# radiata_v1.net
KiCad netlist of a schematic drawn in EAGLE
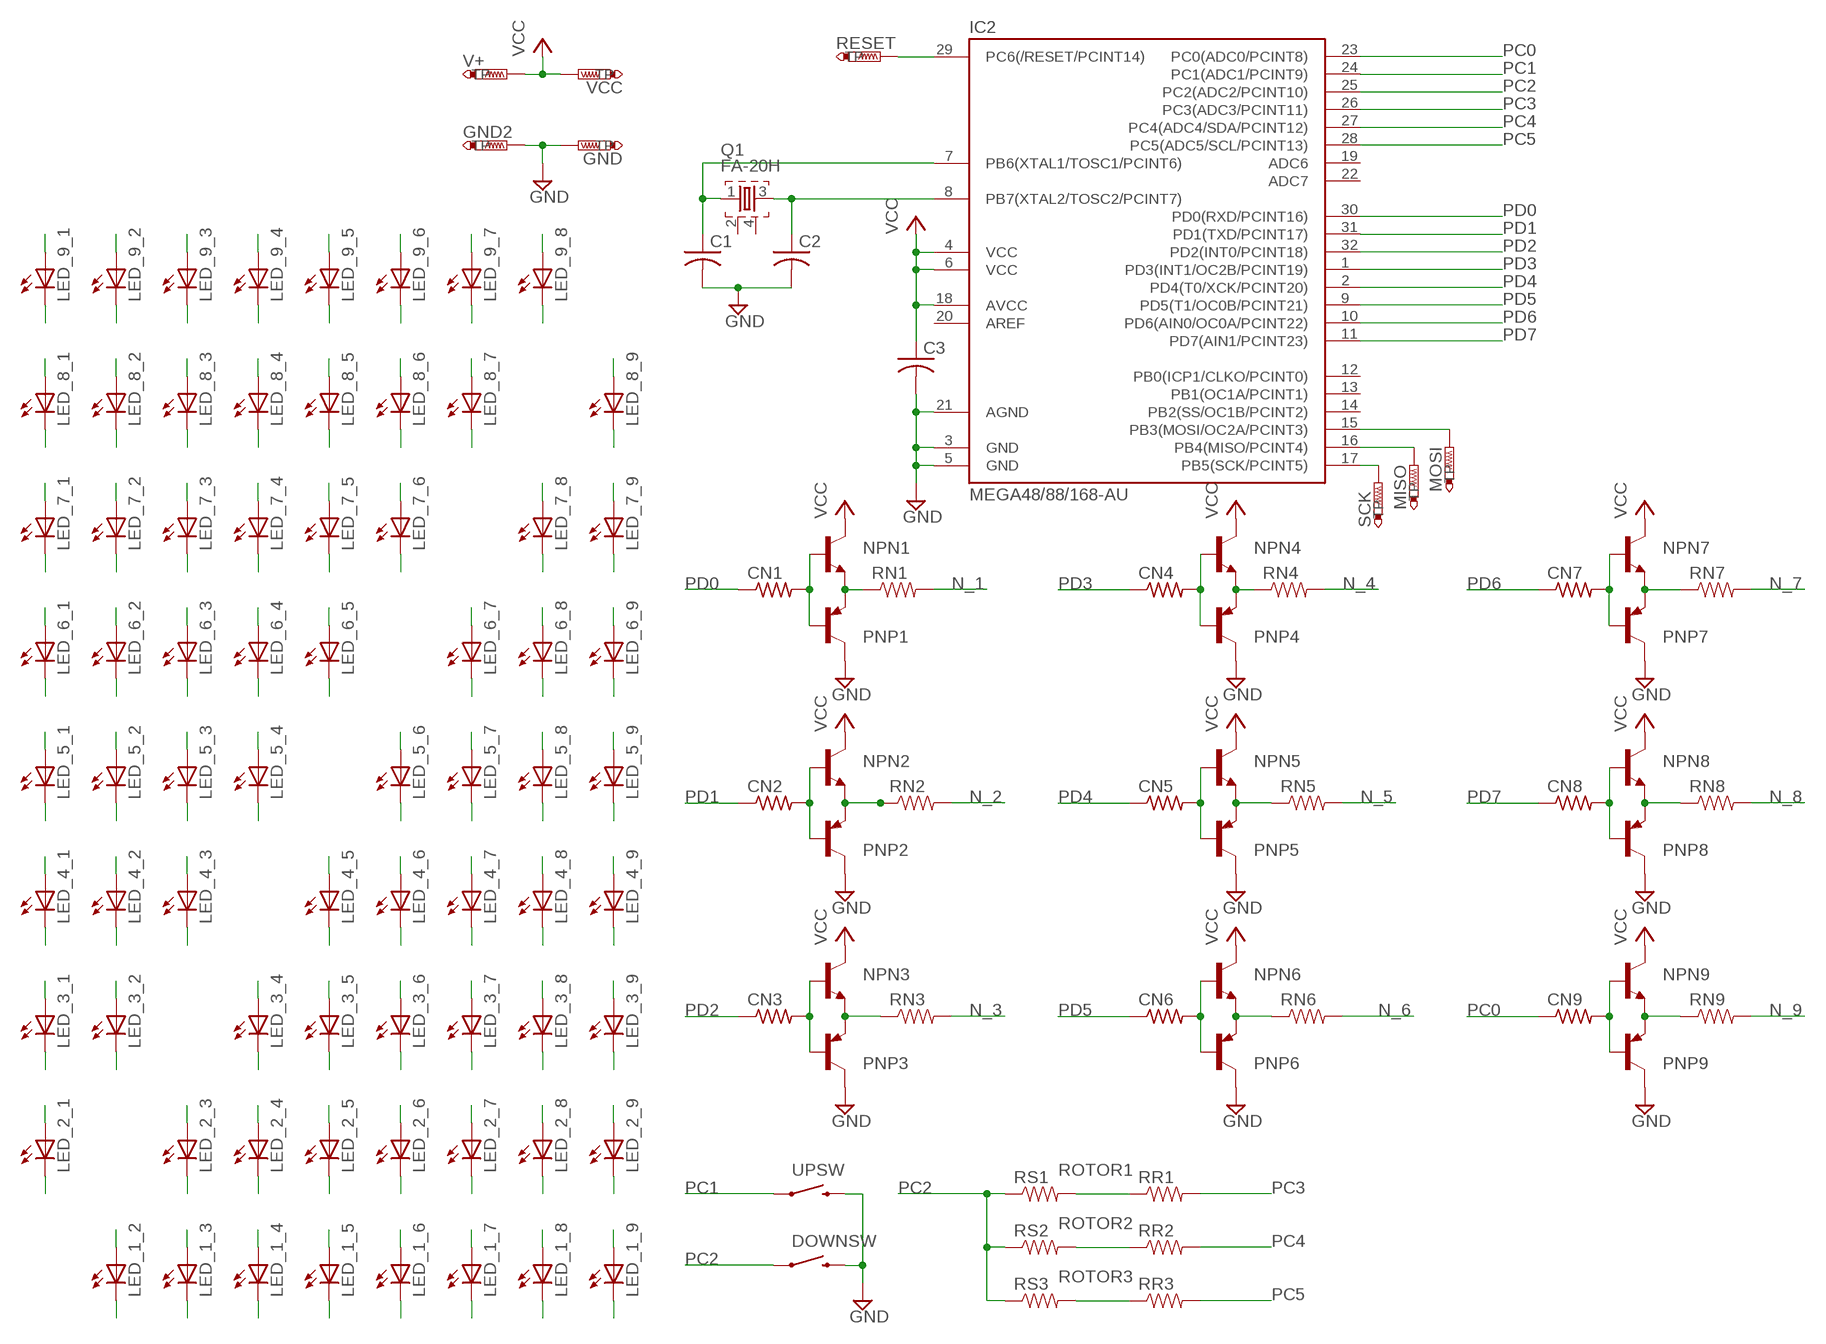
[diagram p0: schematic, sheet 1]

(export (version "E")
  (design (tool "Eeschema 10.0.6"))
  (components
    (comp (ref "C1")
      (value "C-USC0603")
      (footprint "eagle-import:C0603")
      (libsource (lib "eagle-import") (part "C-USC0603"))
    )
    (comp (ref "C2")
      (value "C-USC0603")
      (footprint "eagle-import:C0603")
      (libsource (lib "eagle-import") (part "C-USC0603"))
    )
    (comp (ref "C3")
      (value "C-USC0603")
      (footprint "eagle-import:C0603")
      (libsource (lib "eagle-import") (part "C-USC0603"))
    )
    (comp (ref "CN1")
      (value "R-US_M0805")
      (footprint "eagle-import:M0805")
      (libsource (lib "eagle-import") (part "R-US_M0805"))
    )
    (comp (ref "CN2")
      (value "R-US_M0805")
      (footprint "eagle-import:M0805")
      (libsource (lib "eagle-import") (part "R-US_M0805"))
    )
    (comp (ref "CN3")
      (value "R-US_M0805")
      (footprint "eagle-import:M0805")
      (libsource (lib "eagle-import") (part "R-US_M0805"))
    )
    (comp (ref "CN4")
      (value "R-US_M0805")
      (footprint "eagle-import:M0805")
      (libsource (lib "eagle-import") (part "R-US_M0805"))
    )
    (comp (ref "CN5")
      (value "R-US_M0805")
      (footprint "eagle-import:M0805")
      (libsource (lib "eagle-import") (part "R-US_M0805"))
    )
    (comp (ref "CN6")
      (value "R-US_M0805")
      (footprint "eagle-import:M0805")
      (libsource (lib "eagle-import") (part "R-US_M0805"))
    )
    (comp (ref "CN7")
      (value "R-US_M0805")
      (footprint "eagle-import:M0805")
      (libsource (lib "eagle-import") (part "R-US_M0805"))
    )
    (comp (ref "CN8")
      (value "R-US_M0805")
      (footprint "eagle-import:M0805")
      (libsource (lib "eagle-import") (part "R-US_M0805"))
    )
    (comp (ref "CN9")
      (value "R-US_M0805")
      (footprint "eagle-import:M0805")
      (libsource (lib "eagle-import") (part "R-US_M0805"))
    )
    (comp (ref "DOWNSW")
      (value "SWITCH-MOMENTARY-2")
      (footprint "eagle-import:TACTILE_SWITCH_TALL")
      (libsource (lib "eagle-import") (part "SWITCH-MOMENTARY-2"))
    )
    (comp (ref "GND")
      (value "PTR1TP19R")
      (footprint "eagle-import:TP19R")
      (libsource (lib "eagle-import") (part "PTR1TP19R"))
    )
    (comp (ref "GND2")
      (value "PTR1TP20SQ")
      (footprint "eagle-import:TP20SQ")
      (libsource (lib "eagle-import") (part "PTR1TP20SQ"))
    )
    (comp (ref "IC2")
      (value "MEGA48/88/168-AU")
      (footprint "eagle-import:TQFP32-08")
      (libsource (lib "eagle-import") (part "MEGA48/88/168-AU"))
    )
    (comp (ref "LED_1_2")
      (value "LEDCHIPLED_1206")
      (footprint "eagle-import:CHIPLED_1206")
      (libsource (lib "eagle-import") (part "LEDCHIPLED_1206"))
    )
    (comp (ref "LED_1_3")
      (value "LEDCHIPLED_1206")
      (footprint "eagle-import:CHIPLED_1206")
      (libsource (lib "eagle-import") (part "LEDCHIPLED_1206"))
    )
    (comp (ref "LED_1_4")
      (value "LEDCHIPLED_1206")
      (footprint "eagle-import:CHIPLED_1206")
      (libsource (lib "eagle-import") (part "LEDCHIPLED_1206"))
    )
    (comp (ref "LED_1_5")
      (value "LEDCHIPLED_1206")
      (footprint "eagle-import:CHIPLED_1206")
      (libsource (lib "eagle-import") (part "LEDCHIPLED_1206"))
    )
    (comp (ref "LED_1_6")
      (value "LEDCHIPLED_1206")
      (footprint "eagle-import:CHIPLED_1206")
      (libsource (lib "eagle-import") (part "LEDCHIPLED_1206"))
    )
    (comp (ref "LED_1_7")
      (value "LEDCHIPLED_1206")
      (footprint "eagle-import:CHIPLED_1206")
      (libsource (lib "eagle-import") (part "LEDCHIPLED_1206"))
    )
    (comp (ref "LED_1_8")
      (value "LEDCHIPLED_1206")
      (footprint "eagle-import:CHIPLED_1206")
      (libsource (lib "eagle-import") (part "LEDCHIPLED_1206"))
    )
    (comp (ref "LED_1_9")
      (value "LEDCHIPLED_1206")
      (footprint "eagle-import:CHIPLED_1206")
      (libsource (lib "eagle-import") (part "LEDCHIPLED_1206"))
    )
    (comp (ref "LED_2_1")
      (value "LEDCHIPLED_1206")
      (footprint "eagle-import:CHIPLED_1206")
      (libsource (lib "eagle-import") (part "LEDCHIPLED_1206"))
    )
    (comp (ref "LED_2_3")
      (value "LEDCHIPLED_1206")
      (footprint "eagle-import:CHIPLED_1206")
      (libsource (lib "eagle-import") (part "LEDCHIPLED_1206"))
    )
    (comp (ref "LED_2_4")
      (value "LEDCHIPLED_1206")
      (footprint "eagle-import:CHIPLED_1206")
      (libsource (lib "eagle-import") (part "LEDCHIPLED_1206"))
    )
    (comp (ref "LED_2_5")
      (value "LEDCHIPLED_1206")
      (footprint "eagle-import:CHIPLED_1206")
      (libsource (lib "eagle-import") (part "LEDCHIPLED_1206"))
    )
    (comp (ref "LED_2_6")
      (value "LEDCHIPLED_1206")
      (footprint "eagle-import:CHIPLED_1206")
      (libsource (lib "eagle-import") (part "LEDCHIPLED_1206"))
    )
    (comp (ref "LED_2_7")
      (value "LEDCHIPLED_1206")
      (footprint "eagle-import:CHIPLED_1206")
      (libsource (lib "eagle-import") (part "LEDCHIPLED_1206"))
    )
    (comp (ref "LED_2_8")
      (value "LEDCHIPLED_1206")
      (footprint "eagle-import:CHIPLED_1206")
      (libsource (lib "eagle-import") (part "LEDCHIPLED_1206"))
    )
    (comp (ref "LED_2_9")
      (value "LEDCHIPLED_1206")
      (footprint "eagle-import:CHIPLED_1206")
      (libsource (lib "eagle-import") (part "LEDCHIPLED_1206"))
    )
    (comp (ref "LED_3_1")
      (value "LEDCHIPLED_1206")
      (footprint "eagle-import:CHIPLED_1206")
      (libsource (lib "eagle-import") (part "LEDCHIPLED_1206"))
    )
    (comp (ref "LED_3_2")
      (value "LEDCHIPLED_1206")
      (footprint "eagle-import:CHIPLED_1206")
      (libsource (lib "eagle-import") (part "LEDCHIPLED_1206"))
    )
    (comp (ref "LED_3_4")
      (value "LEDCHIPLED_1206")
      (footprint "eagle-import:CHIPLED_1206")
      (libsource (lib "eagle-import") (part "LEDCHIPLED_1206"))
    )
    (comp (ref "LED_3_5")
      (value "LEDCHIPLED_1206")
      (footprint "eagle-import:CHIPLED_1206")
      (libsource (lib "eagle-import") (part "LEDCHIPLED_1206"))
    )
    (comp (ref "LED_3_6")
      (value "LEDCHIPLED_1206")
      (footprint "eagle-import:CHIPLED_1206")
      (libsource (lib "eagle-import") (part "LEDCHIPLED_1206"))
    )
    (comp (ref "LED_3_7")
      (value "LEDCHIPLED_1206")
      (footprint "eagle-import:CHIPLED_1206")
      (libsource (lib "eagle-import") (part "LEDCHIPLED_1206"))
    )
    (comp (ref "LED_3_8")
      (value "LEDCHIPLED_1206")
      (footprint "eagle-import:CHIPLED_1206")
      (libsource (lib "eagle-import") (part "LEDCHIPLED_1206"))
    )
    (comp (ref "LED_3_9")
      (value "LEDCHIPLED_1206")
      (footprint "eagle-import:CHIPLED_1206")
      (libsource (lib "eagle-import") (part "LEDCHIPLED_1206"))
    )
    (comp (ref "LED_4_1")
      (value "LEDCHIPLED_1206")
      (footprint "eagle-import:CHIPLED_1206")
      (libsource (lib "eagle-import") (part "LEDCHIPLED_1206"))
    )
    (comp (ref "LED_4_2")
      (value "LEDCHIPLED_1206")
      (footprint "eagle-import:CHIPLED_1206")
      (libsource (lib "eagle-import") (part "LEDCHIPLED_1206"))
    )
    (comp (ref "LED_4_3")
      (value "LEDCHIPLED_1206")
      (footprint "eagle-import:CHIPLED_1206")
      (libsource (lib "eagle-import") (part "LEDCHIPLED_1206"))
    )
    (comp (ref "LED_4_5")
      (value "LEDCHIPLED_1206")
      (footprint "eagle-import:CHIPLED_1206")
      (libsource (lib "eagle-import") (part "LEDCHIPLED_1206"))
    )
    (comp (ref "LED_4_6")
      (value "LEDCHIPLED_1206")
      (footprint "eagle-import:CHIPLED_1206")
      (libsource (lib "eagle-import") (part "LEDCHIPLED_1206"))
    )
    (comp (ref "LED_4_7")
      (value "LEDCHIPLED_1206")
      (footprint "eagle-import:CHIPLED_1206")
      (libsource (lib "eagle-import") (part "LEDCHIPLED_1206"))
    )
    (comp (ref "LED_4_8")
      (value "LEDCHIPLED_1206")
      (footprint "eagle-import:CHIPLED_1206")
      (libsource (lib "eagle-import") (part "LEDCHIPLED_1206"))
    )
    (comp (ref "LED_4_9")
      (value "LEDCHIPLED_1206")
      (footprint "eagle-import:CHIPLED_1206")
      (libsource (lib "eagle-import") (part "LEDCHIPLED_1206"))
    )
    (comp (ref "LED_5_1")
      (value "LEDCHIPLED_1206")
      (footprint "eagle-import:CHIPLED_1206")
      (libsource (lib "eagle-import") (part "LEDCHIPLED_1206"))
    )
    (comp (ref "LED_5_2")
      (value "LEDCHIPLED_1206")
      (footprint "eagle-import:CHIPLED_1206")
      (libsource (lib "eagle-import") (part "LEDCHIPLED_1206"))
    )
    (comp (ref "LED_5_3")
      (value "LEDCHIPLED_1206")
      (footprint "eagle-import:CHIPLED_1206")
      (libsource (lib "eagle-import") (part "LEDCHIPLED_1206"))
    )
    (comp (ref "LED_5_4")
      (value "LEDCHIPLED_1206")
      (footprint "eagle-import:CHIPLED_1206")
      (libsource (lib "eagle-import") (part "LEDCHIPLED_1206"))
    )
    (comp (ref "LED_5_6")
      (value "LEDCHIPLED_1206")
      (footprint "eagle-import:CHIPLED_1206")
      (libsource (lib "eagle-import") (part "LEDCHIPLED_1206"))
    )
    (comp (ref "LED_5_7")
      (value "LEDCHIPLED_1206")
      (footprint "eagle-import:CHIPLED_1206")
      (libsource (lib "eagle-import") (part "LEDCHIPLED_1206"))
    )
    (comp (ref "LED_5_8")
      (value "LEDCHIPLED_1206")
      (footprint "eagle-import:CHIPLED_1206")
      (libsource (lib "eagle-import") (part "LEDCHIPLED_1206"))
    )
    (comp (ref "LED_5_9")
      (value "LEDCHIPLED_1206")
      (footprint "eagle-import:CHIPLED_1206")
      (libsource (lib "eagle-import") (part "LEDCHIPLED_1206"))
    )
    (comp (ref "LED_6_1")
      (value "LEDCHIPLED_1206")
      (footprint "eagle-import:CHIPLED_1206")
      (libsource (lib "eagle-import") (part "LEDCHIPLED_1206"))
    )
    (comp (ref "LED_6_2")
      (value "LEDCHIPLED_1206")
      (footprint "eagle-import:CHIPLED_1206")
      (libsource (lib "eagle-import") (part "LEDCHIPLED_1206"))
    )
    (comp (ref "LED_6_3")
      (value "LEDCHIPLED_1206")
      (footprint "eagle-import:CHIPLED_1206")
      (libsource (lib "eagle-import") (part "LEDCHIPLED_1206"))
    )
    (comp (ref "LED_6_4")
      (value "LEDCHIPLED_1206")
      (footprint "eagle-import:CHIPLED_1206")
      (libsource (lib "eagle-import") (part "LEDCHIPLED_1206"))
    )
    (comp (ref "LED_6_5")
      (value "LEDCHIPLED_1206")
      (footprint "eagle-import:CHIPLED_1206")
      (libsource (lib "eagle-import") (part "LEDCHIPLED_1206"))
    )
    (comp (ref "LED_6_7")
      (value "LEDCHIPLED_1206")
      (footprint "eagle-import:CHIPLED_1206")
      (libsource (lib "eagle-import") (part "LEDCHIPLED_1206"))
    )
    (comp (ref "LED_6_8")
      (value "LEDCHIPLED_1206")
      (footprint "eagle-import:CHIPLED_1206")
      (libsource (lib "eagle-import") (part "LEDCHIPLED_1206"))
    )
    (comp (ref "LED_6_9")
      (value "LEDCHIPLED_1206")
      (footprint "eagle-import:CHIPLED_1206")
      (libsource (lib "eagle-import") (part "LEDCHIPLED_1206"))
    )
    (comp (ref "LED_7_1")
      (value "LEDCHIPLED_1206")
      (footprint "eagle-import:CHIPLED_1206")
      (libsource (lib "eagle-import") (part "LEDCHIPLED_1206"))
    )
    (comp (ref "LED_7_2")
      (value "LEDCHIPLED_1206")
      (footprint "eagle-import:CHIPLED_1206")
      (libsource (lib "eagle-import") (part "LEDCHIPLED_1206"))
    )
    (comp (ref "LED_7_3")
      (value "LEDCHIPLED_1206")
      (footprint "eagle-import:CHIPLED_1206")
      (libsource (lib "eagle-import") (part "LEDCHIPLED_1206"))
    )
    (comp (ref "LED_7_4")
      (value "LEDCHIPLED_1206")
      (footprint "eagle-import:CHIPLED_1206")
      (libsource (lib "eagle-import") (part "LEDCHIPLED_1206"))
    )
    (comp (ref "LED_7_5")
      (value "LEDCHIPLED_1206")
      (footprint "eagle-import:CHIPLED_1206")
      (libsource (lib "eagle-import") (part "LEDCHIPLED_1206"))
    )
    (comp (ref "LED_7_6")
      (value "LEDCHIPLED_1206")
      (footprint "eagle-import:CHIPLED_1206")
      (libsource (lib "eagle-import") (part "LEDCHIPLED_1206"))
    )
    (comp (ref "LED_7_8")
      (value "LEDCHIPLED_1206")
      (footprint "eagle-import:CHIPLED_1206")
      (libsource (lib "eagle-import") (part "LEDCHIPLED_1206"))
    )
    (comp (ref "LED_7_9")
      (value "LEDCHIPLED_1206")
      (footprint "eagle-import:CHIPLED_1206")
      (libsource (lib "eagle-import") (part "LEDCHIPLED_1206"))
    )
    (comp (ref "LED_8_1")
      (value "LEDCHIPLED_1206")
      (footprint "eagle-import:CHIPLED_1206")
      (libsource (lib "eagle-import") (part "LEDCHIPLED_1206"))
    )
    (comp (ref "LED_8_2")
      (value "LEDCHIPLED_1206")
      (footprint "eagle-import:CHIPLED_1206")
      (libsource (lib "eagle-import") (part "LEDCHIPLED_1206"))
    )
    (comp (ref "LED_8_3")
      (value "LEDCHIPLED_1206")
      (footprint "eagle-import:CHIPLED_1206")
      (libsource (lib "eagle-import") (part "LEDCHIPLED_1206"))
    )
    (comp (ref "LED_8_4")
      (value "LEDCHIPLED_1206")
      (footprint "eagle-import:CHIPLED_1206")
      (libsource (lib "eagle-import") (part "LEDCHIPLED_1206"))
    )
    (comp (ref "LED_8_5")
      (value "LEDCHIPLED_1206")
      (footprint "eagle-import:CHIPLED_1206")
      (libsource (lib "eagle-import") (part "LEDCHIPLED_1206"))
    )
    (comp (ref "LED_8_6")
      (value "LEDCHIPLED_1206")
      (footprint "eagle-import:CHIPLED_1206")
      (libsource (lib "eagle-import") (part "LEDCHIPLED_1206"))
    )
    (comp (ref "LED_8_7")
      (value "LEDCHIPLED_1206")
      (footprint "eagle-import:CHIPLED_1206")
      (libsource (lib "eagle-import") (part "LEDCHIPLED_1206"))
    )
    (comp (ref "LED_8_9")
      (value "LEDCHIPLED_1206")
      (footprint "eagle-import:CHIPLED_1206")
      (libsource (lib "eagle-import") (part "LEDCHIPLED_1206"))
    )
    (comp (ref "LED_9_1")
      (value "LEDCHIPLED_1206")
      (footprint "eagle-import:CHIPLED_1206")
      (libsource (lib "eagle-import") (part "LEDCHIPLED_1206"))
    )
    (comp (ref "LED_9_2")
      (value "LEDCHIPLED_1206")
      (footprint "eagle-import:CHIPLED_1206")
      (libsource (lib "eagle-import") (part "LEDCHIPLED_1206"))
    )
    (comp (ref "LED_9_3")
      (value "LEDCHIPLED_1206")
      (footprint "eagle-import:CHIPLED_1206")
      (libsource (lib "eagle-import") (part "LEDCHIPLED_1206"))
    )
    (comp (ref "LED_9_4")
      (value "LEDCHIPLED_1206")
      (footprint "eagle-import:CHIPLED_1206")
      (libsource (lib "eagle-import") (part "LEDCHIPLED_1206"))
    )
    (comp (ref "LED_9_5")
      (value "LEDCHIPLED_1206")
      (footprint "eagle-import:CHIPLED_1206")
      (libsource (lib "eagle-import") (part "LEDCHIPLED_1206"))
    )
    (comp (ref "LED_9_6")
      (value "LEDCHIPLED_1206")
      (footprint "eagle-import:CHIPLED_1206")
      (libsource (lib "eagle-import") (part "LEDCHIPLED_1206"))
    )
    (comp (ref "LED_9_7")
      (value "LEDCHIPLED_1206")
      (footprint "eagle-import:CHIPLED_1206")
      (libsource (lib "eagle-import") (part "LEDCHIPLED_1206"))
    )
    (comp (ref "LED_9_8")
      (value "LEDCHIPLED_1206")
      (footprint "eagle-import:CHIPLED_1206")
      (libsource (lib "eagle-import") (part "LEDCHIPLED_1206"))
    )
    (comp (ref "MISO")
      (value "PTR1TP19R")
      (footprint "eagle-import:TP19R")
      (libsource (lib "eagle-import") (part "PTR1TP19R"))
    )
    (comp (ref "MOSI")
      (value "PTR1TP19R")
      (footprint "eagle-import:TP19R")
      (libsource (lib "eagle-import") (part "PTR1TP19R"))
    )
    (comp (ref "NPN1")
      (value "MMBT2222ALT1-NPN-SOT23-BEC")
      (footprint "eagle-import:SOT23-BEC")
      (libsource (lib "eagle-import") (part "-NPN-SOT23-BECMMBT2222ALT1"))
    )
    (comp (ref "NPN2")
      (value "MMBT2222ALT1-NPN-SOT23-BEC")
      (footprint "eagle-import:SOT23-BEC")
      (libsource (lib "eagle-import") (part "-NPN-SOT23-BECMMBT2222ALT1"))
    )
    (comp (ref "NPN3")
      (value "MMBT2222ALT1-NPN-SOT23-BEC")
      (footprint "eagle-import:SOT23-BEC")
      (libsource (lib "eagle-import") (part "-NPN-SOT23-BECMMBT2222ALT1"))
    )
    (comp (ref "NPN4")
      (value "MMBT2222ALT1-NPN-SOT23-BEC")
      (footprint "eagle-import:SOT23-BEC")
      (libsource (lib "eagle-import") (part "-NPN-SOT23-BECMMBT2222ALT1"))
    )
    (comp (ref "NPN5")
      (value "MMBT2222ALT1-NPN-SOT23-BEC")
      (footprint "eagle-import:SOT23-BEC")
      (libsource (lib "eagle-import") (part "-NPN-SOT23-BECMMBT2222ALT1"))
    )
    (comp (ref "NPN6")
      (value "MMBT2222ALT1-NPN-SOT23-BEC")
      (footprint "eagle-import:SOT23-BEC")
      (libsource (lib "eagle-import") (part "-NPN-SOT23-BECMMBT2222ALT1"))
    )
    (comp (ref "NPN7")
      (value "MMBT2222ALT1-NPN-SOT23-BEC")
      (footprint "eagle-import:SOT23-BEC")
      (libsource (lib "eagle-import") (part "-NPN-SOT23-BECMMBT2222ALT1"))
    )
    (comp (ref "NPN8")
      (value "MMBT2222ALT1-NPN-SOT23-BEC")
      (footprint "eagle-import:SOT23-BEC")
      (libsource (lib "eagle-import") (part "-NPN-SOT23-BECMMBT2222ALT1"))
    )
    (comp (ref "NPN9")
      (value "MMBT2222ALT1-NPN-SOT23-BEC")
      (footprint "eagle-import:SOT23-BEC")
      (libsource (lib "eagle-import") (part "-NPN-SOT23-BECMMBT2222ALT1"))
    )
    (comp (ref "PNP1")
      (value "MMBT2907ALT1-PNP-SOT23-BEC")
      (footprint "eagle-import:SOT23-BEC")
      (libsource (lib "eagle-import") (part "-PNP-SOT23-BECMMBT2907ALT1"))
    )
    (comp (ref "PNP2")
      (value "MMBT2907ALT1-PNP-SOT23-BEC")
      (footprint "eagle-import:SOT23-BEC")
      (libsource (lib "eagle-import") (part "-PNP-SOT23-BECMMBT2907ALT1"))
    )
    (comp (ref "PNP3")
      (value "MMBT2907ALT1-PNP-SOT23-BEC")
      (footprint "eagle-import:SOT23-BEC")
      (libsource (lib "eagle-import") (part "-PNP-SOT23-BECMMBT2907ALT1"))
    )
    (comp (ref "PNP4")
      (value "MMBT2907ALT1-PNP-SOT23-BEC")
      (footprint "eagle-import:SOT23-BEC")
      (libsource (lib "eagle-import") (part "-PNP-SOT23-BECMMBT2907ALT1"))
    )
    (comp (ref "PNP5")
      (value "MMBT2907ALT1-PNP-SOT23-BEC")
      (footprint "eagle-import:SOT23-BEC")
      (libsource (lib "eagle-import") (part "-PNP-SOT23-BECMMBT2907ALT1"))
    )
    (comp (ref "PNP6")
      (value "MMBT2907ALT1-PNP-SOT23-BEC")
      (footprint "eagle-import:SOT23-BEC")
      (libsource (lib "eagle-import") (part "-PNP-SOT23-BECMMBT2907ALT1"))
    )
    (comp (ref "PNP7")
      (value "MMBT2907ALT1-PNP-SOT23-BEC")
      (footprint "eagle-import:SOT23-BEC")
      (libsource (lib "eagle-import") (part "-PNP-SOT23-BECMMBT2907ALT1"))
    )
    (comp (ref "PNP8")
      (value "MMBT2907ALT1-PNP-SOT23-BEC")
      (footprint "eagle-import:SOT23-BEC")
      (libsource (lib "eagle-import") (part "-PNP-SOT23-BECMMBT2907ALT1"))
    )
    (comp (ref "PNP9")
      (value "MMBT2907ALT1-PNP-SOT23-BEC")
      (footprint "eagle-import:SOT23-BEC")
      (libsource (lib "eagle-import") (part "-PNP-SOT23-BECMMBT2907ALT1"))
    )
    (comp (ref "Q1")
      (value "FA-20H")
      (footprint "eagle-import:FA-20H")
      (libsource (lib "eagle-import") (part "FA-20H"))
    )
    (comp (ref "RESET")
      (value "PTR1TP19R")
      (footprint "eagle-import:TP19R")
      (libsource (lib "eagle-import") (part "PTR1TP19R"))
    )
    (comp (ref "RN1")
      (value "RESISTOR1206")
      (footprint "eagle-import:1206")
      (libsource (lib "eagle-import") (part "RESISTOR1206"))
    )
    (comp (ref "RN2")
      (value "RESISTOR1206")
      (footprint "eagle-import:1206")
      (libsource (lib "eagle-import") (part "RESISTOR1206"))
    )
    (comp (ref "RN3")
      (value "RESISTOR1206")
      (footprint "eagle-import:1206")
      (libsource (lib "eagle-import") (part "RESISTOR1206"))
    )
    (comp (ref "RN4")
      (value "RESISTOR1206")
      (footprint "eagle-import:1206")
      (libsource (lib "eagle-import") (part "RESISTOR1206"))
    )
    (comp (ref "RN5")
      (value "RESISTOR1206")
      (footprint "eagle-import:1206")
      (libsource (lib "eagle-import") (part "RESISTOR1206"))
    )
    (comp (ref "RN6")
      (value "RESISTOR1206")
      (footprint "eagle-import:1206")
      (libsource (lib "eagle-import") (part "RESISTOR1206"))
    )
    (comp (ref "RN7")
      (value "RESISTOR1206")
      (footprint "eagle-import:1206")
      (libsource (lib "eagle-import") (part "RESISTOR1206"))
    )
    (comp (ref "RN8")
      (value "RESISTOR1206")
      (footprint "eagle-import:1206")
      (libsource (lib "eagle-import") (part "RESISTOR1206"))
    )
    (comp (ref "RN9")
      (value "RESISTOR1206")
      (footprint "eagle-import:1206")
      (libsource (lib "eagle-import") (part "RESISTOR1206"))
    )
    (comp (ref "RR1")
      (value "RESISTOR1206")
      (footprint "eagle-import:1206")
      (libsource (lib "eagle-import") (part "RESISTOR1206"))
    )
    (comp (ref "RR2")
      (value "RESISTOR1206")
      (footprint "eagle-import:1206")
      (libsource (lib "eagle-import") (part "RESISTOR1206"))
    )
    (comp (ref "RR3")
      (value "RESISTOR1206")
      (footprint "eagle-import:1206")
      (libsource (lib "eagle-import") (part "RESISTOR1206"))
    )
    (comp (ref "RS1")
      (value "RESISTOR1206")
      (footprint "eagle-import:1206")
      (libsource (lib "eagle-import") (part "RESISTOR1206"))
    )
    (comp (ref "RS2")
      (value "RESISTOR1206")
      (footprint "eagle-import:1206")
      (libsource (lib "eagle-import") (part "RESISTOR1206"))
    )
    (comp (ref "RS3")
      (value "RESISTOR1206")
      (footprint "eagle-import:1206")
      (libsource (lib "eagle-import") (part "RESISTOR1206"))
    )
    (comp (ref "SCK")
      (value "PTR1TP19R")
      (footprint "eagle-import:TP19R")
      (libsource (lib "eagle-import") (part "PTR1TP19R"))
    )
    (comp (ref "UPSW")
      (value "SWITCH-MOMENTARY-2")
      (footprint "eagle-import:TACTILE_SWITCH_TALL")
      (libsource (lib "eagle-import") (part "SWITCH-MOMENTARY-2"))
    )
    (comp (ref "V+")
      (value "PTR1TP20SQ")
      (footprint "eagle-import:TP20SQ")
      (libsource (lib "eagle-import") (part "PTR1TP20SQ"))
    )
    (comp (ref "VCC")
      (value "PTR1TP19R")
      (footprint "eagle-import:TP19R")
      (libsource (lib "eagle-import") (part "PTR1TP19R"))
    )
  )
  (nets
    (net (code "1") (name "/N_1") (class "Default")
      (node (ref "LED_1_2") (pin "A") (pinfunction "A_A") (pintype "passive"))
      (node (ref "LED_1_3") (pin "A") (pinfunction "A_A") (pintype "passive"))
      (node (ref "LED_1_4") (pin "A") (pinfunction "A_A") (pintype "passive"))
      (node (ref "LED_1_5") (pin "A") (pinfunction "A_A") (pintype "passive"))
      (node (ref "LED_1_6") (pin "A") (pinfunction "A_A") (pintype "passive"))
      (node (ref "LED_1_7") (pin "A") (pinfunction "A_A") (pintype "passive"))
      (node (ref "LED_1_8") (pin "A") (pinfunction "A_A") (pintype "passive"))
      (node (ref "LED_1_9") (pin "A") (pinfunction "A_A") (pintype "passive"))
      (node (ref "LED_2_1") (pin "C") (pinfunction "C_C") (pintype "passive"))
      (node (ref "LED_3_1") (pin "C") (pinfunction "C_C") (pintype "passive"))
      (node (ref "LED_4_1") (pin "C") (pinfunction "C_C") (pintype "passive"))
      (node (ref "LED_5_1") (pin "C") (pinfunction "C_C") (pintype "passive"))
      (node (ref "LED_6_1") (pin "C") (pinfunction "C_C") (pintype "passive"))
      (node (ref "LED_7_1") (pin "C") (pinfunction "C_C") (pintype "passive"))
      (node (ref "LED_8_1") (pin "C") (pinfunction "C_C") (pintype "passive"))
      (node (ref "LED_9_1") (pin "C") (pinfunction "C_C") (pintype "passive"))
      (node (ref "RN1") (pin "2") (pinfunction "2_2") (pintype "passive"))
    )
    (net (code "2") (name "/N_2") (class "Default")
      (node (ref "LED_1_2") (pin "C") (pinfunction "C_C") (pintype "passive"))
      (node (ref "LED_2_1") (pin "A") (pinfunction "A_A") (pintype "passive"))
      (node (ref "LED_2_3") (pin "A") (pinfunction "A_A") (pintype "passive"))
      (node (ref "LED_2_4") (pin "A") (pinfunction "A_A") (pintype "passive"))
      (node (ref "LED_2_5") (pin "A") (pinfunction "A_A") (pintype "passive"))
      (node (ref "LED_2_6") (pin "A") (pinfunction "A_A") (pintype "passive"))
      (node (ref "LED_2_7") (pin "A") (pinfunction "A_A") (pintype "passive"))
      (node (ref "LED_2_8") (pin "A") (pinfunction "A_A") (pintype "passive"))
      (node (ref "LED_2_9") (pin "A") (pinfunction "A_A") (pintype "passive"))
      (node (ref "LED_3_2") (pin "C") (pinfunction "C_C") (pintype "passive"))
      (node (ref "LED_4_2") (pin "C") (pinfunction "C_C") (pintype "passive"))
      (node (ref "LED_5_2") (pin "C") (pinfunction "C_C") (pintype "passive"))
      (node (ref "LED_6_2") (pin "C") (pinfunction "C_C") (pintype "passive"))
      (node (ref "LED_7_2") (pin "C") (pinfunction "C_C") (pintype "passive"))
      (node (ref "LED_8_2") (pin "C") (pinfunction "C_C") (pintype "passive"))
      (node (ref "LED_9_2") (pin "C") (pinfunction "C_C") (pintype "passive"))
      (node (ref "RN2") (pin "2") (pinfunction "2_2") (pintype "passive"))
    )
    (net (code "3") (name "/N_3") (class "Default")
      (node (ref "LED_1_3") (pin "C") (pinfunction "C_C") (pintype "passive"))
      (node (ref "LED_2_3") (pin "C") (pinfunction "C_C") (pintype "passive"))
      (node (ref "LED_3_1") (pin "A") (pinfunction "A_A") (pintype "passive"))
      (node (ref "LED_3_2") (pin "A") (pinfunction "A_A") (pintype "passive"))
      (node (ref "LED_3_4") (pin "A") (pinfunction "A_A") (pintype "passive"))
      (node (ref "LED_3_5") (pin "A") (pinfunction "A_A") (pintype "passive"))
      (node (ref "LED_3_6") (pin "A") (pinfunction "A_A") (pintype "passive"))
      (node (ref "LED_3_7") (pin "A") (pinfunction "A_A") (pintype "passive"))
      (node (ref "LED_3_8") (pin "A") (pinfunction "A_A") (pintype "passive"))
      (node (ref "LED_3_9") (pin "A") (pinfunction "A_A") (pintype "passive"))
      (node (ref "LED_4_3") (pin "C") (pinfunction "C_C") (pintype "passive"))
      (node (ref "LED_5_3") (pin "C") (pinfunction "C_C") (pintype "passive"))
      (node (ref "LED_6_3") (pin "C") (pinfunction "C_C") (pintype "passive"))
      (node (ref "LED_7_3") (pin "C") (pinfunction "C_C") (pintype "passive"))
      (node (ref "LED_8_3") (pin "C") (pinfunction "C_C") (pintype "passive"))
      (node (ref "LED_9_3") (pin "C") (pinfunction "C_C") (pintype "passive"))
      (node (ref "RN3") (pin "2") (pinfunction "2_2") (pintype "passive"))
    )
    (net (code "4") (name "/N_4") (class "Default")
      (node (ref "LED_1_4") (pin "C") (pinfunction "C_C") (pintype "passive"))
      (node (ref "LED_2_4") (pin "C") (pinfunction "C_C") (pintype "passive"))
      (node (ref "LED_3_4") (pin "C") (pinfunction "C_C") (pintype "passive"))
      (node (ref "LED_4_1") (pin "A") (pinfunction "A_A") (pintype "passive"))
      (node (ref "LED_4_2") (pin "A") (pinfunction "A_A") (pintype "passive"))
      (node (ref "LED_4_3") (pin "A") (pinfunction "A_A") (pintype "passive"))
      (node (ref "LED_4_5") (pin "A") (pinfunction "A_A") (pintype "passive"))
      (node (ref "LED_4_6") (pin "A") (pinfunction "A_A") (pintype "passive"))
      (node (ref "LED_4_7") (pin "A") (pinfunction "A_A") (pintype "passive"))
      (node (ref "LED_4_8") (pin "A") (pinfunction "A_A") (pintype "passive"))
      (node (ref "LED_4_9") (pin "A") (pinfunction "A_A") (pintype "passive"))
      (node (ref "LED_5_4") (pin "C") (pinfunction "C_C") (pintype "passive"))
      (node (ref "LED_6_4") (pin "C") (pinfunction "C_C") (pintype "passive"))
      (node (ref "LED_7_4") (pin "C") (pinfunction "C_C") (pintype "passive"))
      (node (ref "LED_8_4") (pin "C") (pinfunction "C_C") (pintype "passive"))
      (node (ref "LED_9_4") (pin "C") (pinfunction "C_C") (pintype "passive"))
      (node (ref "RN4") (pin "2") (pinfunction "2_2") (pintype "passive"))
    )
    (net (code "5") (name "/N_5") (class "Default")
      (node (ref "LED_1_5") (pin "C") (pinfunction "C_C") (pintype "passive"))
      (node (ref "LED_2_5") (pin "C") (pinfunction "C_C") (pintype "passive"))
      (node (ref "LED_3_5") (pin "C") (pinfunction "C_C") (pintype "passive"))
      (node (ref "LED_4_5") (pin "C") (pinfunction "C_C") (pintype "passive"))
      (node (ref "LED_5_1") (pin "A") (pinfunction "A_A") (pintype "passive"))
      (node (ref "LED_5_2") (pin "A") (pinfunction "A_A") (pintype "passive"))
      (node (ref "LED_5_3") (pin "A") (pinfunction "A_A") (pintype "passive"))
      (node (ref "LED_5_4") (pin "A") (pinfunction "A_A") (pintype "passive"))
      (node (ref "LED_5_6") (pin "A") (pinfunction "A_A") (pintype "passive"))
      (node (ref "LED_5_7") (pin "A") (pinfunction "A_A") (pintype "passive"))
      (node (ref "LED_5_8") (pin "A") (pinfunction "A_A") (pintype "passive"))
      (node (ref "LED_5_9") (pin "A") (pinfunction "A_A") (pintype "passive"))
      (node (ref "LED_6_5") (pin "C") (pinfunction "C_C") (pintype "passive"))
      (node (ref "LED_7_5") (pin "C") (pinfunction "C_C") (pintype "passive"))
      (node (ref "LED_8_5") (pin "C") (pinfunction "C_C") (pintype "passive"))
      (node (ref "LED_9_5") (pin "C") (pinfunction "C_C") (pintype "passive"))
      (node (ref "RN5") (pin "2") (pinfunction "2_2") (pintype "passive"))
    )
    (net (code "6") (name "/N_6") (class "Default")
      (node (ref "LED_1_6") (pin "C") (pinfunction "C_C") (pintype "passive"))
      (node (ref "LED_2_6") (pin "C") (pinfunction "C_C") (pintype "passive"))
      (node (ref "LED_3_6") (pin "C") (pinfunction "C_C") (pintype "passive"))
      (node (ref "LED_4_6") (pin "C") (pinfunction "C_C") (pintype "passive"))
      (node (ref "LED_5_6") (pin "C") (pinfunction "C_C") (pintype "passive"))
      (node (ref "LED_6_1") (pin "A") (pinfunction "A_A") (pintype "passive"))
      (node (ref "LED_6_2") (pin "A") (pinfunction "A_A") (pintype "passive"))
      (node (ref "LED_6_3") (pin "A") (pinfunction "A_A") (pintype "passive"))
      (node (ref "LED_6_4") (pin "A") (pinfunction "A_A") (pintype "passive"))
      (node (ref "LED_6_5") (pin "A") (pinfunction "A_A") (pintype "passive"))
      (node (ref "LED_6_7") (pin "A") (pinfunction "A_A") (pintype "passive"))
      (node (ref "LED_6_8") (pin "A") (pinfunction "A_A") (pintype "passive"))
      (node (ref "LED_6_9") (pin "A") (pinfunction "A_A") (pintype "passive"))
      (node (ref "LED_7_6") (pin "C") (pinfunction "C_C") (pintype "passive"))
      (node (ref "LED_8_6") (pin "C") (pinfunction "C_C") (pintype "passive"))
      (node (ref "LED_9_6") (pin "C") (pinfunction "C_C") (pintype "passive"))
      (node (ref "RN6") (pin "2") (pinfunction "2_2") (pintype "passive"))
    )
    (net (code "7") (name "/N_7") (class "Default")
      (node (ref "LED_1_7") (pin "C") (pinfunction "C_C") (pintype "passive"))
      (node (ref "LED_2_7") (pin "C") (pinfunction "C_C") (pintype "passive"))
      (node (ref "LED_3_7") (pin "C") (pinfunction "C_C") (pintype "passive"))
      (node (ref "LED_4_7") (pin "C") (pinfunction "C_C") (pintype "passive"))
      (node (ref "LED_5_7") (pin "C") (pinfunction "C_C") (pintype "passive"))
      (node (ref "LED_6_7") (pin "C") (pinfunction "C_C") (pintype "passive"))
      (node (ref "LED_7_1") (pin "A") (pinfunction "A_A") (pintype "passive"))
      (node (ref "LED_7_2") (pin "A") (pinfunction "A_A") (pintype "passive"))
      (node (ref "LED_7_3") (pin "A") (pinfunction "A_A") (pintype "passive"))
      (node (ref "LED_7_4") (pin "A") (pinfunction "A_A") (pintype "passive"))
      (node (ref "LED_7_5") (pin "A") (pinfunction "A_A") (pintype "passive"))
      (node (ref "LED_7_6") (pin "A") (pinfunction "A_A") (pintype "passive"))
      (node (ref "LED_7_8") (pin "A") (pinfunction "A_A") (pintype "passive"))
      (node (ref "LED_7_9") (pin "A") (pinfunction "A_A") (pintype "passive"))
      (node (ref "LED_8_7") (pin "C") (pinfunction "C_C") (pintype "passive"))
      (node (ref "LED_9_7") (pin "C") (pinfunction "C_C") (pintype "passive"))
      (node (ref "RN7") (pin "2") (pinfunction "2_2") (pintype "passive"))
    )
    (net (code "8") (name "/N_8") (class "Default")
      (node (ref "LED_1_8") (pin "C") (pinfunction "C_C") (pintype "passive"))
      (node (ref "LED_2_8") (pin "C") (pinfunction "C_C") (pintype "passive"))
      (node (ref "LED_3_8") (pin "C") (pinfunction "C_C") (pintype "passive"))
      (node (ref "LED_4_8") (pin "C") (pinfunction "C_C") (pintype "passive"))
      (node (ref "LED_5_8") (pin "C") (pinfunction "C_C") (pintype "passive"))
      (node (ref "LED_6_8") (pin "C") (pinfunction "C_C") (pintype "passive"))
      (node (ref "LED_7_8") (pin "C") (pinfunction "C_C") (pintype "passive"))
      (node (ref "LED_8_1") (pin "A") (pinfunction "A_A") (pintype "passive"))
      (node (ref "LED_8_2") (pin "A") (pinfunction "A_A") (pintype "passive"))
      (node (ref "LED_8_3") (pin "A") (pinfunction "A_A") (pintype "passive"))
      (node (ref "LED_8_4") (pin "A") (pinfunction "A_A") (pintype "passive"))
      (node (ref "LED_8_5") (pin "A") (pinfunction "A_A") (pintype "passive"))
      (node (ref "LED_8_6") (pin "A") (pinfunction "A_A") (pintype "passive"))
      (node (ref "LED_8_7") (pin "A") (pinfunction "A_A") (pintype "passive"))
      (node (ref "LED_8_9") (pin "A") (pinfunction "A_A") (pintype "passive"))
      (node (ref "LED_9_8") (pin "C") (pinfunction "C_C") (pintype "passive"))
      (node (ref "RN8") (pin "2") (pinfunction "2_2") (pintype "passive"))
    )
    (net (code "9") (name "/N_9") (class "Default")
      (node (ref "LED_1_9") (pin "C") (pinfunction "C_C") (pintype "passive"))
      (node (ref "LED_2_9") (pin "C") (pinfunction "C_C") (pintype "passive"))
      (node (ref "LED_3_9") (pin "C") (pinfunction "C_C") (pintype "passive"))
      (node (ref "LED_4_9") (pin "C") (pinfunction "C_C") (pintype "passive"))
      (node (ref "LED_5_9") (pin "C") (pinfunction "C_C") (pintype "passive"))
      (node (ref "LED_6_9") (pin "C") (pinfunction "C_C") (pintype "passive"))
      (node (ref "LED_7_9") (pin "C") (pinfunction "C_C") (pintype "passive"))
      (node (ref "LED_8_9") (pin "C") (pinfunction "C_C") (pintype "passive"))
      (node (ref "LED_9_1") (pin "A") (pinfunction "A_A") (pintype "passive"))
      (node (ref "LED_9_2") (pin "A") (pinfunction "A_A") (pintype "passive"))
      (node (ref "LED_9_3") (pin "A") (pinfunction "A_A") (pintype "passive"))
      (node (ref "LED_9_4") (pin "A") (pinfunction "A_A") (pintype "passive"))
      (node (ref "LED_9_5") (pin "A") (pinfunction "A_A") (pintype "passive"))
      (node (ref "LED_9_6") (pin "A") (pinfunction "A_A") (pintype "passive"))
      (node (ref "LED_9_7") (pin "A") (pinfunction "A_A") (pintype "passive"))
      (node (ref "LED_9_8") (pin "A") (pinfunction "A_A") (pintype "passive"))
      (node (ref "RN9") (pin "2") (pinfunction "2_2") (pintype "passive"))
    )
    (net (code "10") (name "/PC0") (class "Default")
      (node (ref "CN9") (pin "1") (pinfunction "1_1") (pintype "passive"))
      (node (ref "IC2") (pin "23") (pinfunction "PC0(ADC0/PCINT8)_23") (pintype "bidirectional"))
    )
    (net (code "11") (name "/PC1") (class "Default")
      (node (ref "IC2") (pin "24") (pinfunction "PC1(ADC1/PCINT9)_24") (pintype "bidirectional"))
      (node (ref "UPSW") (pin "A2") (pinfunction "1_A2") (pintype "passive"))
    )
    (net (code "12") (name "/PC2") (class "Default")
      (node (ref "DOWNSW") (pin "A2") (pinfunction "1_A2") (pintype "passive"))
      (node (ref "IC2") (pin "25") (pinfunction "PC2(ADC2/PCINT10)_25") (pintype "bidirectional"))
      (node (ref "RS1") (pin "1") (pinfunction "1_1") (pintype "passive"))
      (node (ref "RS2") (pin "1") (pinfunction "1_1") (pintype "passive"))
      (node (ref "RS3") (pin "1") (pinfunction "1_1") (pintype "passive"))
    )
    (net (code "13") (name "/PC3") (class "Default")
      (node (ref "IC2") (pin "26") (pinfunction "PC3(ADC3/PCINT11)_26") (pintype "bidirectional"))
      (node (ref "RR1") (pin "2") (pinfunction "2_2") (pintype "passive"))
    )
    (net (code "14") (name "/PC4") (class "Default")
      (node (ref "IC2") (pin "27") (pinfunction "PC4(ADC4/SDA/PCINT12)_27") (pintype "bidirectional"))
      (node (ref "RR2") (pin "2") (pinfunction "2_2") (pintype "passive"))
    )
    (net (code "15") (name "/PC5") (class "Default")
      (node (ref "IC2") (pin "28") (pinfunction "PC5(ADC5/SCL/PCINT13)_28") (pintype "bidirectional"))
      (node (ref "RR3") (pin "2") (pinfunction "2_2") (pintype "passive"))
    )
    (net (code "16") (name "/PD0") (class "Default")
      (node (ref "CN1") (pin "1") (pinfunction "1_1") (pintype "passive"))
      (node (ref "IC2") (pin "30") (pinfunction "PD0(RXD/PCINT16)_30") (pintype "bidirectional"))
    )
    (net (code "17") (name "/PD1") (class "Default")
      (node (ref "CN2") (pin "1") (pinfunction "1_1") (pintype "passive"))
      (node (ref "IC2") (pin "31") (pinfunction "PD1(TXD/PCINT17)_31") (pintype "bidirectional"))
    )
    (net (code "18") (name "/PD2") (class "Default")
      (node (ref "CN3") (pin "1") (pinfunction "1_1") (pintype "passive"))
      (node (ref "IC2") (pin "32") (pinfunction "PD2(INT0/PCINT18)_32") (pintype "bidirectional"))
    )
    (net (code "19") (name "/PD3") (class "Default")
      (node (ref "CN4") (pin "1") (pinfunction "1_1") (pintype "passive"))
      (node (ref "IC2") (pin "1") (pinfunction "PD3(INT1/OC2B/PCINT19)_1") (pintype "bidirectional"))
    )
    (net (code "20") (name "/PD4") (class "Default")
      (node (ref "CN5") (pin "1") (pinfunction "1_1") (pintype "passive"))
      (node (ref "IC2") (pin "2") (pinfunction "PD4(T0/XCK/PCINT20)_2") (pintype "bidirectional"))
    )
    (net (code "21") (name "/PD5") (class "Default")
      (node (ref "CN6") (pin "1") (pinfunction "1_1") (pintype "passive"))
      (node (ref "IC2") (pin "9") (pinfunction "PD5(T1/OC0B/PCINT21)_9") (pintype "bidirectional"))
    )
    (net (code "22") (name "/PD6") (class "Default")
      (node (ref "CN7") (pin "1") (pinfunction "1_1") (pintype "passive"))
      (node (ref "IC2") (pin "10") (pinfunction "PD6(AIN0/OC0A/PCINT22)_10") (pintype "bidirectional"))
    )
    (net (code "23") (name "/PD7") (class "Default")
      (node (ref "CN8") (pin "1") (pinfunction "1_1") (pintype "passive"))
      (node (ref "IC2") (pin "11") (pinfunction "PD7(AIN1/PCINT23)_11") (pintype "bidirectional"))
    )
    (net (code "24") (name "/ROTOR1") (class "Default")
      (node (ref "RR1") (pin "1") (pinfunction "1_1") (pintype "passive"))
      (node (ref "RS1") (pin "2") (pinfunction "2_2") (pintype "passive"))
    )
    (net (code "25") (name "/ROTOR2") (class "Default")
      (node (ref "RR2") (pin "1") (pinfunction "1_1") (pintype "passive"))
      (node (ref "RS2") (pin "2") (pinfunction "2_2") (pintype "passive"))
    )
    (net (code "26") (name "/ROTOR3") (class "Default")
      (node (ref "RR3") (pin "1") (pinfunction "1_1") (pintype "passive"))
      (node (ref "RS3") (pin "2") (pinfunction "2_2") (pintype "passive"))
    )
    (net (code "27") (name "GND") (class "Default")
      (node (ref "C1") (pin "2") (pinfunction "2_2") (pintype "passive"))
      (node (ref "C2") (pin "2") (pinfunction "2_2") (pintype "passive"))
      (node (ref "C3") (pin "2") (pinfunction "2_2") (pintype "passive"))
      (node (ref "DOWNSW") (pin "B2") (pinfunction "2_B2") (pintype "passive"))
      (node (ref "GND") (pin "TP") (pinfunction "TP_TP") (pintype "input"))
      (node (ref "GND2") (pin "TP") (pinfunction "TP_TP") (pintype "input"))
      (node (ref "IC2") (pin "21") (pinfunction "AGND_21") (pintype "power_in"))
      (node (ref "IC2") (pin "3") (pinfunction "GND_3") (pintype "power_in"))
      (node (ref "IC2") (pin "5") (pinfunction "GND_5") (pintype "power_in"))
      (node (ref "PNP1") (pin "C") (pinfunction "C_C") (pintype "passive"))
      (node (ref "PNP2") (pin "C") (pinfunction "C_C") (pintype "passive"))
      (node (ref "PNP3") (pin "C") (pinfunction "C_C") (pintype "passive"))
      (node (ref "PNP4") (pin "C") (pinfunction "C_C") (pintype "passive"))
      (node (ref "PNP5") (pin "C") (pinfunction "C_C") (pintype "passive"))
      (node (ref "PNP6") (pin "C") (pinfunction "C_C") (pintype "passive"))
      (node (ref "PNP7") (pin "C") (pinfunction "C_C") (pintype "passive"))
      (node (ref "PNP8") (pin "C") (pinfunction "C_C") (pintype "passive"))
      (node (ref "PNP9") (pin "C") (pinfunction "C_C") (pintype "passive"))
      (node (ref "UPSW") (pin "B2") (pinfunction "2_B2") (pintype "passive"))
    )
    (net (code "28") (name "Net-(CN1-Pad2)") (class "Default")
      (node (ref "CN1") (pin "2") (pinfunction "2_2") (pintype "passive"))
      (node (ref "NPN1") (pin "B") (pinfunction "B_B") (pintype "passive"))
      (node (ref "PNP1") (pin "B") (pinfunction "B_B") (pintype "passive"))
    )
    (net (code "29") (name "Net-(CN2-Pad2)") (class "Default")
      (node (ref "CN2") (pin "2") (pinfunction "2_2") (pintype "passive"))
      (node (ref "NPN2") (pin "B") (pinfunction "B_B") (pintype "passive"))
      (node (ref "PNP2") (pin "B") (pinfunction "B_B") (pintype "passive"))
    )
    (net (code "30") (name "Net-(CN3-Pad2)") (class "Default")
      (node (ref "CN3") (pin "2") (pinfunction "2_2") (pintype "passive"))
      (node (ref "NPN3") (pin "B") (pinfunction "B_B") (pintype "passive"))
      (node (ref "PNP3") (pin "B") (pinfunction "B_B") (pintype "passive"))
    )
    (net (code "31") (name "Net-(CN4-Pad2)") (class "Default")
      (node (ref "CN4") (pin "2") (pinfunction "2_2") (pintype "passive"))
      (node (ref "NPN4") (pin "B") (pinfunction "B_B") (pintype "passive"))
      (node (ref "PNP4") (pin "B") (pinfunction "B_B") (pintype "passive"))
    )
    (net (code "32") (name "Net-(CN5-Pad2)") (class "Default")
      (node (ref "CN5") (pin "2") (pinfunction "2_2") (pintype "passive"))
      (node (ref "NPN5") (pin "B") (pinfunction "B_B") (pintype "passive"))
      (node (ref "PNP5") (pin "B") (pinfunction "B_B") (pintype "passive"))
    )
    (net (code "33") (name "Net-(CN6-Pad2)") (class "Default")
      (node (ref "CN6") (pin "2") (pinfunction "2_2") (pintype "passive"))
      (node (ref "NPN6") (pin "B") (pinfunction "B_B") (pintype "passive"))
      (node (ref "PNP6") (pin "B") (pinfunction "B_B") (pintype "passive"))
    )
    (net (code "34") (name "Net-(CN7-Pad2)") (class "Default")
      (node (ref "CN7") (pin "2") (pinfunction "2_2") (pintype "passive"))
      (node (ref "NPN7") (pin "B") (pinfunction "B_B") (pintype "passive"))
      (node (ref "PNP7") (pin "B") (pinfunction "B_B") (pintype "passive"))
    )
    (net (code "35") (name "Net-(CN8-Pad2)") (class "Default")
      (node (ref "CN8") (pin "2") (pinfunction "2_2") (pintype "passive"))
      (node (ref "NPN8") (pin "B") (pinfunction "B_B") (pintype "passive"))
      (node (ref "PNP8") (pin "B") (pinfunction "B_B") (pintype "passive"))
    )
    (net (code "36") (name "Net-(CN9-Pad2)") (class "Default")
      (node (ref "CN9") (pin "2") (pinfunction "2_2") (pintype "passive"))
      (node (ref "NPN9") (pin "B") (pinfunction "B_B") (pintype "passive"))
      (node (ref "PNP9") (pin "B") (pinfunction "B_B") (pintype "passive"))
    )
    (net (code "37") (name "Net-(IC2-PB3(MOSI{slash}OC2A{slash}PCINT3))") (class "Default")
      (node (ref "IC2") (pin "15") (pinfunction "PB3(MOSI/OC2A/PCINT3)_15") (pintype "bidirectional"))
      (node (ref "MOSI") (pin "TP") (pinfunction "TP_TP") (pintype "input"))
    )
    (net (code "38") (name "Net-(IC2-PB4(MISO{slash}PCINT4))") (class "Default")
      (node (ref "IC2") (pin "16") (pinfunction "PB4(MISO/PCINT4)_16") (pintype "bidirectional"))
      (node (ref "MISO") (pin "TP") (pinfunction "TP_TP") (pintype "input"))
    )
    (net (code "39") (name "Net-(IC2-PB5(SCK{slash}PCINT5))") (class "Default")
      (node (ref "IC2") (pin "17") (pinfunction "PB5(SCK/PCINT5)_17") (pintype "bidirectional"))
      (node (ref "SCK") (pin "TP") (pinfunction "TP_TP") (pintype "input"))
    )
    (net (code "40") (name "Net-(IC2-PB6(XTAL1{slash}TOSC1{slash}PCINT6))") (class "Default")
      (node (ref "C1") (pin "1") (pinfunction "1_1") (pintype "passive"))
      (node (ref "IC2") (pin "7") (pinfunction "PB6(XTAL1/TOSC1/PCINT6)_7") (pintype "bidirectional"))
      (node (ref "Q1") (pin "1") (pinfunction "1_1") (pintype "passive"))
    )
    (net (code "41") (name "Net-(IC2-PB7(XTAL2{slash}TOSC2{slash}PCINT7))") (class "Default")
      (node (ref "C2") (pin "1") (pinfunction "1_1") (pintype "passive"))
      (node (ref "IC2") (pin "8") (pinfunction "PB7(XTAL2/TOSC2/PCINT7)_8") (pintype "bidirectional"))
      (node (ref "Q1") (pin "3") (pinfunction "3_3") (pintype "passive"))
    )
    (net (code "42") (name "Net-(IC2-PC6({slash}RESET{slash}PCINT14))") (class "Default")
      (node (ref "IC2") (pin "29") (pinfunction "PC6(/RESET/PCINT14)_29") (pintype "bidirectional"))
      (node (ref "RESET") (pin "TP") (pinfunction "TP_TP") (pintype "input"))
    )
    (net (code "43") (name "Net-(NPN1-PadE)") (class "Default")
      (node (ref "NPN1") (pin "E") (pinfunction "E_E") (pintype "passive"))
      (node (ref "PNP1") (pin "E") (pinfunction "E_E") (pintype "passive"))
      (node (ref "RN1") (pin "1") (pinfunction "1_1") (pintype "passive"))
    )
    (net (code "44") (name "Net-(NPN2-PadE)") (class "Default")
      (node (ref "NPN2") (pin "E") (pinfunction "E_E") (pintype "passive"))
      (node (ref "PNP2") (pin "E") (pinfunction "E_E") (pintype "passive"))
      (node (ref "RN2") (pin "1") (pinfunction "1_1") (pintype "passive"))
    )
    (net (code "45") (name "Net-(NPN3-PadE)") (class "Default")
      (node (ref "NPN3") (pin "E") (pinfunction "E_E") (pintype "passive"))
      (node (ref "PNP3") (pin "E") (pinfunction "E_E") (pintype "passive"))
      (node (ref "RN3") (pin "1") (pinfunction "1_1") (pintype "passive"))
    )
    (net (code "46") (name "Net-(NPN4-PadE)") (class "Default")
      (node (ref "NPN4") (pin "E") (pinfunction "E_E") (pintype "passive"))
      (node (ref "PNP4") (pin "E") (pinfunction "E_E") (pintype "passive"))
      (node (ref "RN4") (pin "1") (pinfunction "1_1") (pintype "passive"))
    )
    (net (code "47") (name "Net-(NPN5-PadE)") (class "Default")
      (node (ref "NPN5") (pin "E") (pinfunction "E_E") (pintype "passive"))
      (node (ref "PNP5") (pin "E") (pinfunction "E_E") (pintype "passive"))
      (node (ref "RN5") (pin "1") (pinfunction "1_1") (pintype "passive"))
    )
    (net (code "48") (name "Net-(NPN6-PadE)") (class "Default")
      (node (ref "NPN6") (pin "E") (pinfunction "E_E") (pintype "passive"))
      (node (ref "PNP6") (pin "E") (pinfunction "E_E") (pintype "passive"))
      (node (ref "RN6") (pin "1") (pinfunction "1_1") (pintype "passive"))
    )
    (net (code "49") (name "Net-(NPN7-PadE)") (class "Default")
      (node (ref "NPN7") (pin "E") (pinfunction "E_E") (pintype "passive"))
      (node (ref "PNP7") (pin "E") (pinfunction "E_E") (pintype "passive"))
      (node (ref "RN7") (pin "1") (pinfunction "1_1") (pintype "passive"))
    )
    (net (code "50") (name "Net-(NPN8-PadE)") (class "Default")
      (node (ref "NPN8") (pin "E") (pinfunction "E_E") (pintype "passive"))
      (node (ref "PNP8") (pin "E") (pinfunction "E_E") (pintype "passive"))
      (node (ref "RN8") (pin "1") (pinfunction "1_1") (pintype "passive"))
    )
    (net (code "51") (name "Net-(NPN9-PadE)") (class "Default")
      (node (ref "NPN9") (pin "E") (pinfunction "E_E") (pintype "passive"))
      (node (ref "PNP9") (pin "E") (pinfunction "E_E") (pintype "passive"))
      (node (ref "RN9") (pin "1") (pinfunction "1_1") (pintype "passive"))
    )
    (net (code "52") (name "VCC") (class "Default")
      (node (ref "C3") (pin "1") (pinfunction "1_1") (pintype "passive"))
      (node (ref "IC2") (pin "18") (pinfunction "AVCC_18") (pintype "passive"))
      (node (ref "IC2") (pin "4") (pinfunction "VCC_4") (pintype "power_in"))
      (node (ref "IC2") (pin "6") (pinfunction "VCC_6") (pintype "power_in"))
      (node (ref "NPN1") (pin "C") (pinfunction "C_C") (pintype "passive"))
      (node (ref "NPN2") (pin "C") (pinfunction "C_C") (pintype "passive"))
      (node (ref "NPN3") (pin "C") (pinfunction "C_C") (pintype "passive"))
      (node (ref "NPN4") (pin "C") (pinfunction "C_C") (pintype "passive"))
      (node (ref "NPN5") (pin "C") (pinfunction "C_C") (pintype "passive"))
      (node (ref "NPN6") (pin "C") (pinfunction "C_C") (pintype "passive"))
      (node (ref "NPN7") (pin "C") (pinfunction "C_C") (pintype "passive"))
      (node (ref "NPN8") (pin "C") (pinfunction "C_C") (pintype "passive"))
      (node (ref "NPN9") (pin "C") (pinfunction "C_C") (pintype "passive"))
      (node (ref "V+") (pin "TP") (pinfunction "TP_TP") (pintype "input"))
      (node (ref "VCC") (pin "TP") (pinfunction "TP_TP") (pintype "input"))
    )
    (net (code "53") (name "unconnected-(IC2-ADC6-Pad19)") (class "Default")
      (node (ref "IC2") (pin "19") (pinfunction "ADC6_19") (pintype "passive"))
    )
    (net (code "54") (name "unconnected-(IC2-ADC7-Pad22)") (class "Default")
      (node (ref "IC2") (pin "22") (pinfunction "ADC7_22") (pintype "passive"))
    )
    (net (code "55") (name "unconnected-(IC2-AREF-Pad20)") (class "Default")
      (node (ref "IC2") (pin "20") (pinfunction "AREF_20") (pintype "passive"))
    )
    (net (code "56") (name "unconnected-(IC2-PB0(ICP1{slash}CLKO{slash}PCINT0)-Pad12)") (class "Default")
      (node (ref "IC2") (pin "12") (pinfunction "PB0(ICP1/CLKO/PCINT0)_12") (pintype "bidirectional"))
    )
    (net (code "57") (name "unconnected-(IC2-PB1(OC1A{slash}PCINT1)-Pad13)") (class "Default")
      (node (ref "IC2") (pin "13") (pinfunction "PB1(OC1A/PCINT1)_13") (pintype "bidirectional"))
    )
    (net (code "58") (name "unconnected-(IC2-PB2(SS{slash}OC1B{slash}PCINT2)-Pad14)") (class "Default")
      (node (ref "IC2") (pin "14") (pinfunction "PB2(SS/OC1B/PCINT2)_14") (pintype "bidirectional"))
    )
    (net (code "59") (name "unconnected-(Q1-Pad2)") (class "Default")
      (node (ref "Q1") (pin "2") (pinfunction "2_2") (pintype "passive"))
    )
    (net (code "60") (name "unconnected-(Q1-Pad4)") (class "Default")
      (node (ref "Q1") (pin "4") (pinfunction "4_4") (pintype "passive"))
    )
  )
)
